# Minimum_MCU_sys.net
KiCad netlist of a schematic drawn in Altium Designer
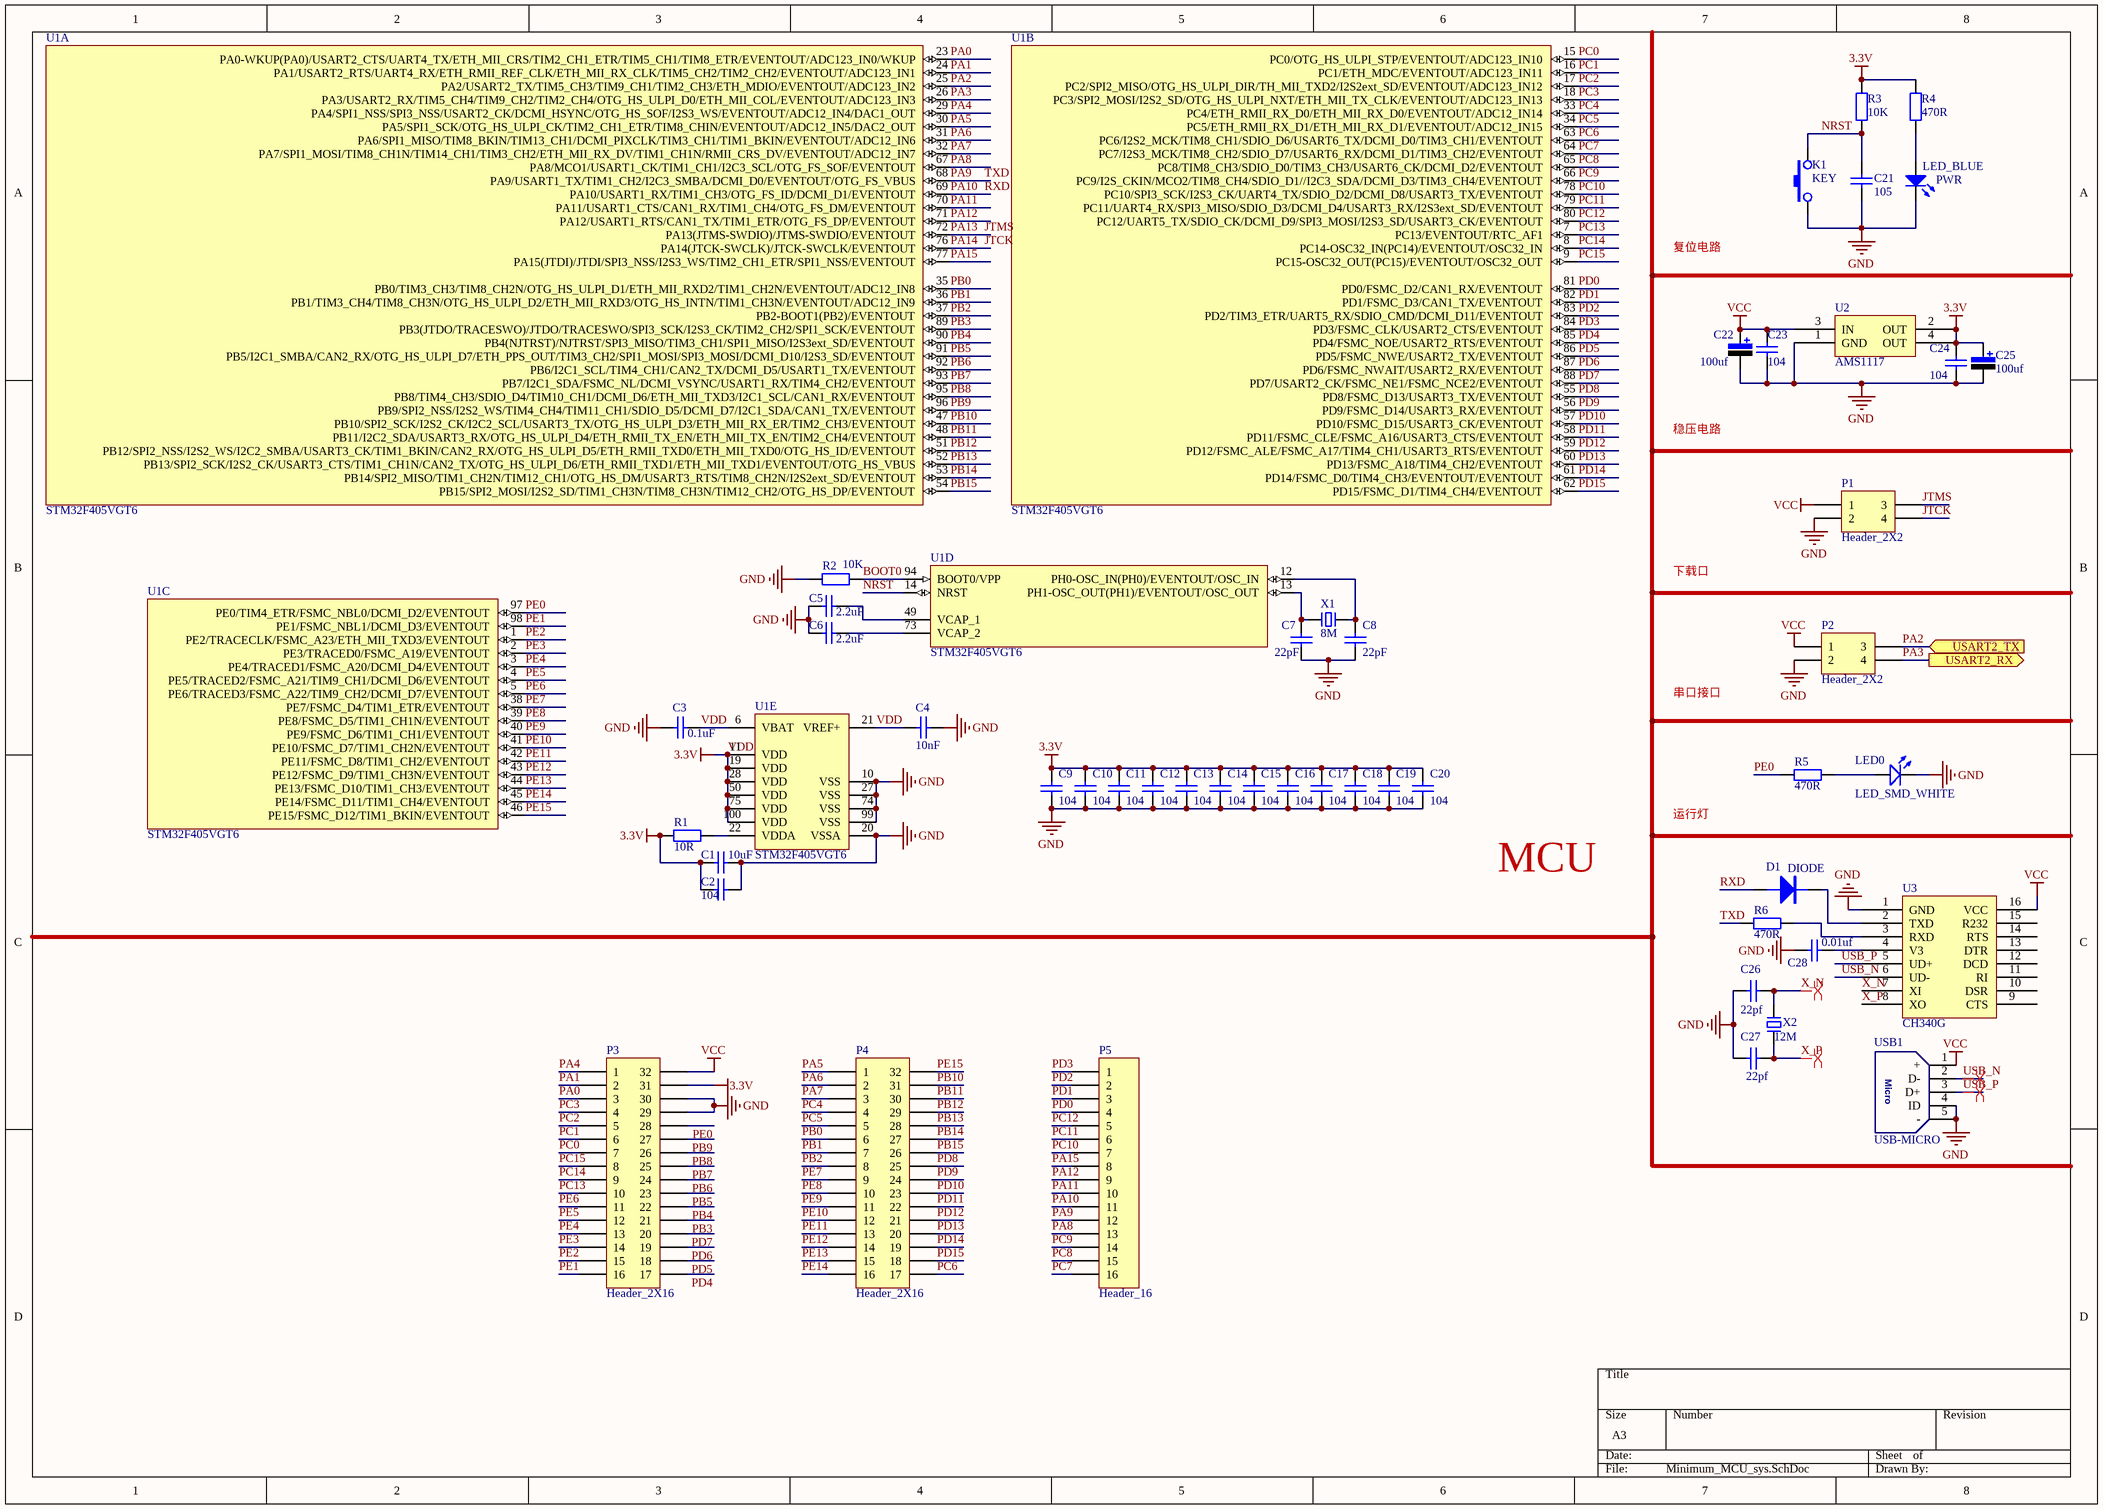
[diagram p0: Minimum_MCU_sys.SchDoc]

(export (version "E")
  (design (tool "Eeschema 10.0.6"))
  (components
    (comp (ref "C1")
      (value "10uF")
      (footprint "Cap-0603")
      (description "贴片陶瓷电容")
      (libsource (lib "Miscellaneous Base") (part "CAP"))
    )
    (comp (ref "C2")
      (value "104")
      (footprint "Cap-0603")
      (description "贴片陶瓷电容")
      (libsource (lib "Miscellaneous Base") (part "CAP"))
    )
    (comp (ref "C3")
      (value "0.1uF")
      (footprint "Cap-0603")
      (description "贴片陶瓷电容")
      (libsource (lib "Miscellaneous Base") (part "CAP"))
    )
    (comp (ref "C4")
      (value "10nF")
      (footprint "Cap-0603")
      (description "贴片陶瓷电容")
      (libsource (lib "Miscellaneous Base") (part "CAP"))
    )
    (comp (ref "C5")
      (value "2.2uF")
      (footprint "Cap-0603")
      (description "贴片陶瓷电容")
      (libsource (lib "Miscellaneous Base") (part "CAP"))
    )
    (comp (ref "C6")
      (value "2.2uF")
      (footprint "Cap-0603")
      (description "贴片陶瓷电容")
      (libsource (lib "Miscellaneous Base") (part "CAP"))
    )
    (comp (ref "C7")
      (value "22pF")
      (footprint "Cap-0603")
      (description "贴片陶瓷电容")
      (libsource (lib "Miscellaneous Base") (part "CAP"))
    )
    (comp (ref "C8")
      (value "22pF")
      (footprint "Cap-0603")
      (description "贴片陶瓷电容")
      (libsource (lib "Miscellaneous Base") (part "CAP"))
    )
    (comp (ref "C9")
      (value "104")
      (footprint "Cap-0603")
      (description "贴片陶瓷电容")
      (libsource (lib "Miscellaneous Base") (part "CAP"))
    )
    (comp (ref "C10")
      (value "104")
      (footprint "Cap-0603")
      (description "贴片陶瓷电容")
      (libsource (lib "Miscellaneous Base") (part "CAP"))
    )
    (comp (ref "C11")
      (value "104")
      (footprint "Cap-0603")
      (description "贴片陶瓷电容")
      (libsource (lib "Miscellaneous Base") (part "CAP"))
    )
    (comp (ref "C12")
      (value "104")
      (footprint "Cap-0603")
      (description "贴片陶瓷电容")
      (libsource (lib "Miscellaneous Base") (part "CAP"))
    )
    (comp (ref "C13")
      (value "104")
      (footprint "Cap-0603")
      (description "贴片陶瓷电容")
      (libsource (lib "Miscellaneous Base") (part "CAP"))
    )
    (comp (ref "C14")
      (value "104")
      (footprint "Cap-0603")
      (description "贴片陶瓷电容")
      (libsource (lib "Miscellaneous Base") (part "CAP"))
    )
    (comp (ref "C15")
      (value "104")
      (footprint "Cap-0603")
      (description "贴片陶瓷电容")
      (libsource (lib "Miscellaneous Base") (part "CAP"))
    )
    (comp (ref "C16")
      (value "104")
      (footprint "Cap-0603")
      (description "贴片陶瓷电容")
      (libsource (lib "Miscellaneous Base") (part "CAP"))
    )
    (comp (ref "C17")
      (value "104")
      (footprint "Cap-0603")
      (description "贴片陶瓷电容")
      (libsource (lib "Miscellaneous Base") (part "CAP"))
    )
    (comp (ref "C18")
      (value "104")
      (footprint "Cap-0603")
      (description "贴片陶瓷电容")
      (libsource (lib "Miscellaneous Base") (part "CAP"))
    )
    (comp (ref "C19")
      (value "104")
      (footprint "Cap-0603")
      (description "贴片陶瓷电容")
      (libsource (lib "Miscellaneous Base") (part "CAP"))
    )
    (comp (ref "C20")
      (value "104")
      (footprint "Cap-0603")
      (description "贴片陶瓷电容")
      (libsource (lib "Miscellaneous Base") (part "CAP"))
    )
    (comp (ref "C21") (value "105") (footprint "Cap-0603") (libsource (lib "最小系统元件库") (part "CAP")))
    (comp (ref "C22") (value "100uf") (footprint "tan_cap_C") (libsource (lib "最小系统元件库") (part "tan_cap")))
    (comp (ref "C23") (value "104") (footprint "Cap-0603-M") (libsource (lib "最小系统元件库") (part "CAP")))
    (comp (ref "C24") (value "104") (footprint "Cap-0603-M") (libsource (lib "最小系统元件库") (part "CAP")))
    (comp (ref "C25") (value "100uf") (footprint "tan_cap_C") (libsource (lib "最小系统元件库") (part "tan_cap")))
    (comp (ref "C26") (value "22pf") (footprint "Cap-0603") (libsource (lib "最小系统元件库") (part "CAP")))
    (comp (ref "C27") (value "22pf") (footprint "Cap-0603") (libsource (lib "最小系统元件库") (part "CAP")))
    (comp (ref "C28") (value "0.01uf") (footprint "Cap-0603") (libsource (lib "base") (part "Cap")))
    (comp (ref "D1")
      (value "DIODE")
      (footprint "SOD-523")
      (description "普通二极管")
      (libsource (lib "Miscellaneous Transistor") (part "DIODE"))
    )
    (comp (ref "K1")
      (value "KEY")
      (footprint "SW-SMD-2X4")
      (libsource (lib "Miscellaneous Switch") (part "KEY"))
    )
    (comp (ref "LED0")
      (value "LED_SMD_WHITE")
      (footprint "LED_0603_W")
      (description "发光二极管")
      (libsource (lib "Miscellaneous Transistor") (part "LED_SMD_WHITE"))
    )
    (comp (ref "P1")
      (value "Header_2X2")
      (footprint "Header_SMD_2.54X2")
      (libsource (lib "Miscellaneous Header") (part "Header_2X2"))
    )
    (comp (ref "P2")
      (value "Header_2X2")
      (footprint "Header_SMD_2.54X2")
      (libsource (lib "Miscellaneous Header") (part "Header_2X2"))
    )
    (comp (ref "P3")
      (value "Header_2X16")
      (footprint "Header 2.54_2X16")
      (libsource (lib "Miscellaneous Header") (part "Header_2X16"))
    )
    (comp (ref "P4")
      (value "Header_2X16")
      (footprint "Header 2.54_2X16")
      (libsource (lib "Miscellaneous Header") (part "Header_2X16"))
    )
    (comp (ref "P5")
      (value "Header_16")
      (footprint "Header 2.54X16")
      (libsource (lib "Miscellaneous Header") (part "Header_16"))
    )
    (comp (ref "PWR")
      (value "LED_BLUE")
      (footprint "LED_0603_B")
      (description "发光二极管")
      (libsource (lib "Miscellaneous Transistor") (part "LED_SMD_BLUE"))
    )
    (comp (ref "R1")
      (value "10R")
      (footprint "Res-0603")
      (description "贴片电阻")
      (libsource (lib "Miscellaneous Base") (part "RES"))
    )
    (comp (ref "R2")
      (value "10K")
      (footprint "Res-0603")
      (description "贴片电阻")
      (libsource (lib "Miscellaneous Base") (part "RES"))
    )
    (comp (ref "R3")
      (value "10K")
      (footprint "Res-0603")
      (description "贴片电阻")
      (libsource (lib "") (part "RES_1"))
    )
    (comp (ref "R4")
      (value "470R")
      (footprint "Res-0603")
      (description "贴片电阻")
      (libsource (lib "") (part "RES_1"))
    )
    (comp (ref "R5")
      (value "470R")
      (footprint "Res-0603")
      (description "贴片电阻")
      (libsource (lib "Miscellaneous Base") (part "RES"))
    )
    (comp (ref "R6")
      (value "470R")
      (footprint "Res-0603")
      (description "贴片电阻")
      (libsource (lib "Miscellaneous Base") (part "RES"))
    )
    (comp (ref "U1")
      (value "STM32F405VGT6")
      (footprint "LQFP100_V")
      (libsource (lib "STMicroelectronics STM32 F4") (part "STM32F405VGT6"))
    )
    (comp (ref "U2") (value "AMS1117") (footprint "AMS1117") (libsource (lib "最小系统元件库") (part "AMS1117")))
    (comp (ref "U3")
      (value "CH340G")
      (footprint "SOP127P590X265-16N")
      (libsource (lib "UperMachineLib") (part "CH340G"))
    )
    (comp (ref "USB1")
      (value "USB-MICRO")
      (footprint "USB-MICRO-SMD_C")
      (libsource (lib "Miscellaneous Socket") (part "USB-MICRO"))
    )
    (comp (ref "X1")
      (value "8M")
      (footprint "OSC 5032-2P")
      (description "2脚无源脚晶振")
      (libsource (lib "Miscellaneous XTAL") (part "XTAL-2P"))
    )
    (comp (ref "X2")
      (value "12M")
      (footprint "OSC 5032-2P")
      (description "2脚无源脚晶振")
      (libsource (lib "Miscellaneous XTAL") (part "XTAL-2P"))
    )
  )
  (nets
    (net (code "1") (name "/BOOT0") (class "Default")
      (node (ref "R2") (pin "2") (pinfunction "2_2") (pintype "passive"))
      (node (ref "U1") (pin "94") (pinfunction "BOOT0/VPP_94") (pintype "input"))
    )
    (net (code "2") (name "/JTCK") (class "Default")
      (node (ref "P1") (pin "4") (pinfunction "4_4") (pintype "passive"))
      (node (ref "U1") (pin "76") (pinfunction "PA14(JTCK-SWCLK)/JTCK-SWCLK/EVENTOUT_76") (pintype "bidirectional"))
    )
    (net (code "3") (name "/JTMS") (class "Default")
      (node (ref "P1") (pin "3") (pinfunction "3_3") (pintype "passive"))
      (node (ref "U1") (pin "72") (pinfunction "PA13(JTMS-SWDIO)/JTMS-SWDIO/EVENTOUT_72") (pintype "bidirectional"))
    )
    (net (code "4") (name "/NRST") (class "Default")
      (node (ref "C21") (pin "2") (pinfunction "2_2") (pintype "passive"))
      (node (ref "K1") (pin "3") (pinfunction "3_3") (pintype "passive"))
      (node (ref "R3") (pin "2") (pinfunction "2_2") (pintype "passive"))
      (node (ref "U1") (pin "14") (pinfunction "NRST_14") (pintype "bidirectional"))
    )
    (net (code "5") (name "/PA0") (class "Default")
      (node (ref "P3") (pin "3") (pinfunction "3_3") (pintype "power_in"))
      (node (ref "U1") (pin "23") (pinfunction "PA0-WKUP(PA0)/USART2_CTS/UART4_TX/ETH_MII_CRS/TIM2_CH1_ETR/TIM5_CH1/TIM8_ETR/EVENTOUT/ADC123_IN0/WKUP_23") (pintype "bidirectional"))
    )
    (net (code "6") (name "/PA1") (class "Default")
      (node (ref "P3") (pin "2") (pinfunction "2_2") (pintype "power_in"))
      (node (ref "U1") (pin "24") (pinfunction "PA1/USART2_RTS/UART4_RX/ETH_RMII_REF_CLK/ETH_MII_RX_CLK/TIM5_CH2/TIM2_CH2/EVENTOUT/ADC123_IN1_24") (pintype "bidirectional"))
    )
    (net (code "7") (name "/PA2") (class "Default")
      (node (ref "P2") (pin "3") (pinfunction "3_3") (pintype "passive"))
      (node (ref "U1") (pin "25") (pinfunction "PA2/USART2_TX/TIM5_CH3/TIM9_CH1/TIM2_CH3/ETH_MDIO/EVENTOUT/ADC123_IN2_25") (pintype "bidirectional"))
    )
    (net (code "8") (name "/PA3") (class "Default")
      (node (ref "P2") (pin "4") (pinfunction "4_4") (pintype "passive"))
      (node (ref "U1") (pin "26") (pinfunction "PA3/USART2_RX/TIM5_CH4/TIM9_CH2/TIM2_CH4/OTG_HS_ULPI_D0/ETH_MII_COL/EVENTOUT/ADC123_IN3_26") (pintype "bidirectional"))
    )
    (net (code "9") (name "/PA4") (class "Default")
      (node (ref "P3") (pin "1") (pinfunction "1_1") (pintype "power_in"))
      (node (ref "U1") (pin "29") (pinfunction "PA4/SPI1_NSS/SPI3_NSS/USART2_CK/DCMI_HSYNC/OTG_HS_SOF/I2S3_WS/EVENTOUT/ADC12_IN4/DAC1_OUT_29") (pintype "bidirectional"))
    )
    (net (code "10") (name "/PA5") (class "Default")
      (node (ref "P4") (pin "1") (pinfunction "1_1") (pintype "power_in"))
      (node (ref "U1") (pin "30") (pinfunction "PA5/SPI1_SCK/OTG_HS_ULPI_CK/TIM2_CH1_ETR/TIM8_CHIN/EVENTOUT/ADC12_IN5/DAC2_OUT_30") (pintype "bidirectional"))
    )
    (net (code "11") (name "/PA6") (class "Default")
      (node (ref "P4") (pin "2") (pinfunction "2_2") (pintype "power_in"))
      (node (ref "U1") (pin "31") (pinfunction "PA6/SPI1_MISO/TIM8_BKIN/TIM13_CH1/DCMI_PIXCLK/TIM3_CH1/TIM1_BKIN/EVENTOUT/ADC12_IN6_31") (pintype "bidirectional"))
    )
    (net (code "12") (name "/PA7") (class "Default")
      (node (ref "P4") (pin "3") (pinfunction "3_3") (pintype "power_in"))
      (node (ref "U1") (pin "32") (pinfunction "PA7/SPI1_MOSI/TIM8_CH1N/TIM14_CH1/TIM3_CH2/ETH_MII_RX_DV/TIM1_CH1N/RMII_CRS_DV/EVENTOUT/ADC12_IN7_32") (pintype "bidirectional"))
    )
    (net (code "13") (name "/PA8") (class "Default")
      (node (ref "P5") (pin "13") (pinfunction "13_13") (pintype "passive"))
      (node (ref "U1") (pin "67") (pinfunction "PA8/MCO1/USART1_CK/TIM1_CH1/I2C3_SCL/OTG_FS_SOF/EVENTOUT_67") (pintype "bidirectional"))
    )
    (net (code "14") (name "/PA9") (class "Default")
      (node (ref "P5") (pin "12") (pinfunction "12_12") (pintype "passive"))
      (node (ref "R6") (pin "1") (pinfunction "1_1") (pintype "passive"))
      (node (ref "U1") (pin "68") (pinfunction "PA9/USART1_TX/TIM1_CH2/I2C3_SMBA/DCMI_D0/EVENTOUT/OTG_FS_VBUS_68") (pintype "bidirectional"))
    )
    (net (code "15") (name "/PA10") (class "Default")
      (node (ref "D1") (pin "A") (pinfunction "A_A") (pintype "passive"))
      (node (ref "P5") (pin "11") (pinfunction "11_11") (pintype "passive"))
      (node (ref "U1") (pin "69") (pinfunction "PA10/USART1_RX/TIM1_CH3/OTG_FS_ID/DCMI_D1/EVENTOUT_69") (pintype "bidirectional"))
    )
    (net (code "16") (name "/PA11") (class "Default")
      (node (ref "P5") (pin "10") (pinfunction "10_10") (pintype "passive"))
      (node (ref "U1") (pin "70") (pinfunction "PA11/USART1_CTS/CAN1_RX/TIM1_CH4/OTG_FS_DM/EVENTOUT_70") (pintype "bidirectional"))
    )
    (net (code "17") (name "/PA12") (class "Default")
      (node (ref "P5") (pin "9") (pinfunction "9_9") (pintype "passive"))
      (node (ref "U1") (pin "71") (pinfunction "PA12/USART1_RTS/CAN1_TX/TIM1_ETR/OTG_FS_DP/EVENTOUT_71") (pintype "bidirectional"))
    )
    (net (code "18") (name "/PA15") (class "Default")
      (node (ref "P5") (pin "8") (pinfunction "8_8") (pintype "passive"))
      (node (ref "U1") (pin "77") (pinfunction "PA15(JTDI)/JTDI/SPI3_NSS/I2S3_WS/TIM2_CH1_ETR/SPI1_NSS/EVENTOUT_77") (pintype "bidirectional"))
    )
    (net (code "19") (name "/PB0") (class "Default")
      (node (ref "P4") (pin "6") (pinfunction "6_6") (pintype "power_in"))
      (node (ref "U1") (pin "35") (pinfunction "PB0/TIM3_CH3/TIM8_CH2N/OTG_HS_ULPI_D1/ETH_MII_RXD2/TIM1_CH2N/EVENTOUT/ADC12_IN8_35") (pintype "bidirectional"))
    )
    (net (code "20") (name "/PB1") (class "Default")
      (node (ref "P4") (pin "7") (pinfunction "7_7") (pintype "power_in"))
      (node (ref "U1") (pin "36") (pinfunction "PB1/TIM3_CH4/TIM8_CH3N/OTG_HS_ULPI_D2/ETH_MII_RXD3/OTG_HS_INTN/TIM1_CH3N/EVENTOUT/ADC12_IN9_36") (pintype "bidirectional"))
    )
    (net (code "21") (name "/PB2") (class "Default")
      (node (ref "P4") (pin "8") (pinfunction "8_8") (pintype "power_in"))
      (node (ref "U1") (pin "37") (pinfunction "PB2-BOOT1(PB2)/EVENTOUT_37") (pintype "bidirectional"))
    )
    (net (code "22") (name "/PB3") (class "Default")
      (node (ref "P3") (pin "21") (pinfunction "21_21") (pintype "power_in"))
      (node (ref "U1") (pin "89") (pinfunction "PB3(JTDO/TRACESWO)/JTDO/TRACESWO/SPI3_SCK/I2S3_CK/TIM2_CH2/SPI1_SCK/EVENTOUT_89") (pintype "bidirectional"))
    )
    (net (code "23") (name "/PB4") (class "Default")
      (node (ref "P3") (pin "22") (pinfunction "22_22") (pintype "power_in"))
      (node (ref "U1") (pin "90") (pinfunction "PB4(NJTRST)/NJTRST/SPI3_MISO/TIM3_CH1/SPI1_MISO/I2S3ext_SD/EVENTOUT_90") (pintype "bidirectional"))
    )
    (net (code "24") (name "/PB5") (class "Default")
      (node (ref "P3") (pin "23") (pinfunction "23_23") (pintype "power_in"))
      (node (ref "U1") (pin "91") (pinfunction "PB5/I2C1_SMBA/CAN2_RX/OTG_HS_ULPI_D7/ETH_PPS_OUT/TIM3_CH2/SPI1_MOSI/SPI3_MOSI/DCMI_D10/I2S3_SD/EVENTOUT_91") (pintype "bidirectional"))
    )
    (net (code "25") (name "/PB6") (class "Default")
      (node (ref "P3") (pin "24") (pinfunction "24_24") (pintype "power_in"))
      (node (ref "U1") (pin "92") (pinfunction "PB6/I2C1_SCL/TIM4_CH1/CAN2_TX/DCMI_D5/USART1_TX/EVENTOUT_92") (pintype "bidirectional"))
    )
    (net (code "26") (name "/PB7") (class "Default")
      (node (ref "P3") (pin "25") (pinfunction "25_25") (pintype "power_in"))
      (node (ref "U1") (pin "93") (pinfunction "PB7/I2C1_SDA/FSMC_NL/DCMI_VSYNC/USART1_RX/TIM4_CH2/EVENTOUT_93") (pintype "bidirectional"))
    )
    (net (code "27") (name "/PB8") (class "Default")
      (node (ref "P3") (pin "26") (pinfunction "26_26") (pintype "power_in"))
      (node (ref "U1") (pin "95") (pinfunction "PB8/TIM4_CH3/SDIO_D4/TIM10_CH1/DCMI_D6/ETH_MII_TXD3/I2C1_SCL/CAN1_RX/EVENTOUT_95") (pintype "bidirectional"))
    )
    (net (code "28") (name "/PB9") (class "Default")
      (node (ref "P3") (pin "27") (pinfunction "27_27") (pintype "power_in"))
      (node (ref "U1") (pin "96") (pinfunction "PB9/SPI2_NSS/I2S2_WS/TIM4_CH4/TIM11_CH1/SDIO_D5/DCMI_D7/I2C1_SDA/CAN1_TX/EVENTOUT_96") (pintype "bidirectional"))
    )
    (net (code "29") (name "/PB10") (class "Default")
      (node (ref "P4") (pin "31") (pinfunction "31_31") (pintype "power_in"))
      (node (ref "U1") (pin "47") (pinfunction "PB10/SPI2_SCK/I2S2_CK/I2C2_SCL/USART3_TX/OTG_HS_ULPI_D3/ETH_MII_RX_ER/TIM2_CH3/EVENTOUT_47") (pintype "bidirectional"))
    )
    (net (code "30") (name "/PB11") (class "Default")
      (node (ref "P4") (pin "30") (pinfunction "30_30") (pintype "power_in"))
      (node (ref "U1") (pin "48") (pinfunction "PB11/I2C2_SDA/USART3_RX/OTG_HS_ULPI_D4/ETH_RMII_TX_EN/ETH_MII_TX_EN/TIM2_CH4/EVENTOUT_48") (pintype "bidirectional"))
    )
    (net (code "31") (name "/PB12") (class "Default")
      (node (ref "P4") (pin "29") (pinfunction "29_29") (pintype "power_in"))
      (node (ref "U1") (pin "51") (pinfunction "PB12/SPI2_NSS/I2S2_WS/I2C2_SMBA/USART3_CK/TIM1_BKIN/CAN2_RX/OTG_HS_ULPI_D5/ETH_RMII_TXD0/ETH_MII_TXD0/OTG_HS_ID/EVENTOUT_51") (pintype "bidirectional"))
    )
    (net (code "32") (name "/PB13") (class "Default")
      (node (ref "P4") (pin "28") (pinfunction "28_28") (pintype "power_in"))
      (node (ref "U1") (pin "52") (pinfunction "PB13/SPI2_SCK/I2S2_CK/USART3_CTS/TIM1_CH1N/CAN2_TX/OTG_HS_ULPI_D6/ETH_RMII_TXD1/ETH_MII_TXD1/EVENTOUT/OTG_HS_VBUS_52") (pintype "bidirectional"))
    )
    (net (code "33") (name "/PB14") (class "Default")
      (node (ref "P4") (pin "27") (pinfunction "27_27") (pintype "power_in"))
      (node (ref "U1") (pin "53") (pinfunction "PB14/SPI2_MISO/TIM1_CH2N/TIM12_CH1/OTG_HS_DM/USART3_RTS/TIM8_CH2N/I2S2ext_SD/EVENTOUT_53") (pintype "bidirectional"))
    )
    (net (code "34") (name "/PB15") (class "Default")
      (node (ref "P4") (pin "26") (pinfunction "26_26") (pintype "power_in"))
      (node (ref "U1") (pin "54") (pinfunction "PB15/SPI2_MOSI/I2S2_SD/TIM1_CH3N/TIM8_CH3N/TIM12_CH2/OTG_HS_DP/EVENTOUT_54") (pintype "bidirectional"))
    )
    (net (code "35") (name "/PC0") (class "Default")
      (node (ref "P3") (pin "7") (pinfunction "7_7") (pintype "power_in"))
      (node (ref "U1") (pin "15") (pinfunction "PC0/OTG_HS_ULPI_STP/EVENTOUT/ADC123_IN10_15") (pintype "bidirectional"))
    )
    (net (code "36") (name "/PC1") (class "Default")
      (node (ref "P3") (pin "6") (pinfunction "6_6") (pintype "power_in"))
      (node (ref "U1") (pin "16") (pinfunction "PC1/ETH_MDC/EVENTOUT/ADC123_IN11_16") (pintype "bidirectional"))
    )
    (net (code "37") (name "/PC2") (class "Default")
      (node (ref "P3") (pin "5") (pinfunction "5_5") (pintype "power_in"))
      (node (ref "U1") (pin "17") (pinfunction "PC2/SPI2_MISO/OTG_HS_ULPI_DIR/TH_MII_TXD2/I2S2ext_SD/EVENTOUT/ADC123_IN12_17") (pintype "bidirectional"))
    )
    (net (code "38") (name "/PC3") (class "Default")
      (node (ref "P3") (pin "4") (pinfunction "4_4") (pintype "power_in"))
      (node (ref "U1") (pin "18") (pinfunction "PC3/SPI2_MOSI/I2S2_SD/OTG_HS_ULPI_NXT/ETH_MII_TX_CLK/EVENTOUT/ADC123_IN13_18") (pintype "bidirectional"))
    )
    (net (code "39") (name "/PC4") (class "Default")
      (node (ref "P4") (pin "4") (pinfunction "4_4") (pintype "power_in"))
      (node (ref "U1") (pin "33") (pinfunction "PC4/ETH_RMII_RX_D0/ETH_MII_RX_D0/EVENTOUT/ADC12_IN14_33") (pintype "bidirectional"))
    )
    (net (code "40") (name "/PC5") (class "Default")
      (node (ref "P4") (pin "5") (pinfunction "5_5") (pintype "power_in"))
      (node (ref "U1") (pin "34") (pinfunction "PC5/ETH_RMII_RX_D1/ETH_MII_RX_D1/EVENTOUT/ADC12_IN15_34") (pintype "bidirectional"))
    )
    (net (code "41") (name "/PC6") (class "Default")
      (node (ref "P4") (pin "17") (pinfunction "17_17") (pintype "power_in"))
      (node (ref "U1") (pin "63") (pinfunction "PC6/I2S2_MCK/TIM8_CH1/SDIO_D6/USART6_TX/DCMI_D0/TIM3_CH1/EVENTOUT_63") (pintype "bidirectional"))
    )
    (net (code "42") (name "/PC7") (class "Default")
      (node (ref "P5") (pin "16") (pinfunction "16_16") (pintype "passive"))
      (node (ref "U1") (pin "64") (pinfunction "PC7/I2S3_MCK/TIM8_CH2/SDIO_D7/USART6_RX/DCMI_D1/TIM3_CH2/EVENTOUT_64") (pintype "bidirectional"))
    )
    (net (code "43") (name "/PC8") (class "Default")
      (node (ref "P5") (pin "15") (pinfunction "15_15") (pintype "passive"))
      (node (ref "U1") (pin "65") (pinfunction "PC8/TIM8_CH3/SDIO_D0/TIM3_CH3/USART6_CK/DCMI_D2/EVENTOUT_65") (pintype "bidirectional"))
    )
    (net (code "44") (name "/PC9") (class "Default")
      (node (ref "P5") (pin "14") (pinfunction "14_14") (pintype "passive"))
      (node (ref "U1") (pin "66") (pinfunction "PC9/I2S_CKIN/MCO2/TIM8_CH4/SDIO_D1//I2C3_SDA/DCMI_D3/TIM3_CH4/EVENTOUT_66") (pintype "bidirectional"))
    )
    (net (code "45") (name "/PC10") (class "Default")
      (node (ref "P5") (pin "7") (pinfunction "7_7") (pintype "passive"))
      (node (ref "U1") (pin "78") (pinfunction "PC10/SPI3_SCK/I2S3_CK/UART4_TX/SDIO_D2/DCMI_D8/USART3_TX/EVENTOUT_78") (pintype "bidirectional"))
    )
    (net (code "46") (name "/PC11") (class "Default")
      (node (ref "P5") (pin "6") (pinfunction "6_6") (pintype "passive"))
      (node (ref "U1") (pin "79") (pinfunction "PC11/UART4_RX/SPI3_MISO/SDIO_D3/DCMI_D4/USART3_RX/I2S3ext_SD/EVENTOUT_79") (pintype "bidirectional"))
    )
    (net (code "47") (name "/PC12") (class "Default")
      (node (ref "P5") (pin "5") (pinfunction "5_5") (pintype "passive"))
      (node (ref "U1") (pin "80") (pinfunction "PC12/UART5_TX/SDIO_CK/DCMI_D9/SPI3_MOSI/I2S3_SD/USART3_CK/EVENTOUT_80") (pintype "bidirectional"))
    )
    (net (code "48") (name "/PC13") (class "Default")
      (node (ref "P3") (pin "10") (pinfunction "10_10") (pintype "power_in"))
      (node (ref "U1") (pin "7") (pinfunction "PC13/EVENTOUT/RTC_AF1_7") (pintype "bidirectional"))
    )
    (net (code "49") (name "/PC14") (class "Default")
      (node (ref "P3") (pin "9") (pinfunction "9_9") (pintype "power_in"))
      (node (ref "U1") (pin "8") (pinfunction "PC14-OSC32_IN(PC14)/EVENTOUT/OSC32_IN_8") (pintype "bidirectional"))
    )
    (net (code "50") (name "/PC15") (class "Default")
      (node (ref "P3") (pin "8") (pinfunction "8_8") (pintype "power_in"))
      (node (ref "U1") (pin "9") (pinfunction "PC15-OSC32_OUT(PC15)/EVENTOUT/OSC32_OUT_9") (pintype "bidirectional"))
    )
    (net (code "51") (name "/PD0") (class "Default")
      (node (ref "P5") (pin "4") (pinfunction "4_4") (pintype "passive"))
      (node (ref "U1") (pin "81") (pinfunction "PD0/FSMC_D2/CAN1_RX/EVENTOUT_81") (pintype "bidirectional"))
    )
    (net (code "52") (name "/PD1") (class "Default")
      (node (ref "P5") (pin "3") (pinfunction "3_3") (pintype "passive"))
      (node (ref "U1") (pin "82") (pinfunction "PD1/FSMC_D3/CAN1_TX/EVENTOUT_82") (pintype "bidirectional"))
    )
    (net (code "53") (name "/PD2") (class "Default")
      (node (ref "P5") (pin "2") (pinfunction "2_2") (pintype "passive"))
      (node (ref "U1") (pin "83") (pinfunction "PD2/TIM3_ETR/UART5_RX/SDIO_CMD/DCMI_D11/EVENTOUT_83") (pintype "bidirectional"))
    )
    (net (code "54") (name "/PD3") (class "Default")
      (node (ref "P5") (pin "1") (pinfunction "1_1") (pintype "passive"))
      (node (ref "U1") (pin "84") (pinfunction "PD3/FSMC_CLK/USART2_CTS/EVENTOUT_84") (pintype "bidirectional"))
    )
    (net (code "55") (name "/PD4") (class "Default")
      (node (ref "P3") (pin "17") (pinfunction "17_17") (pintype "power_in"))
      (node (ref "U1") (pin "85") (pinfunction "PD4/FSMC_NOE/USART2_RTS/EVENTOUT_85") (pintype "bidirectional"))
    )
    (net (code "56") (name "/PD5") (class "Default")
      (node (ref "P3") (pin "18") (pinfunction "18_18") (pintype "power_in"))
      (node (ref "U1") (pin "86") (pinfunction "PD5/FSMC_NWE/USART2_TX/EVENTOUT_86") (pintype "bidirectional"))
    )
    (net (code "57") (name "/PD6") (class "Default")
      (node (ref "P3") (pin "19") (pinfunction "19_19") (pintype "power_in"))
      (node (ref "U1") (pin "87") (pinfunction "PD6/FSMC_NWAIT/USART2_RX/EVENTOUT_87") (pintype "bidirectional"))
    )
    (net (code "58") (name "/PD7") (class "Default")
      (node (ref "P3") (pin "20") (pinfunction "20_20") (pintype "power_in"))
      (node (ref "U1") (pin "88") (pinfunction "PD7/USART2_CK/FSMC_NE1/FSMC_NCE2/EVENTOUT_88") (pintype "bidirectional"))
    )
    (net (code "59") (name "/PD8") (class "Default")
      (node (ref "P4") (pin "25") (pinfunction "25_25") (pintype "power_in"))
      (node (ref "U1") (pin "55") (pinfunction "PD8/FSMC_D13/USART3_TX/EVENTOUT_55") (pintype "bidirectional"))
    )
    (net (code "60") (name "/PD9") (class "Default")
      (node (ref "P4") (pin "24") (pinfunction "24_24") (pintype "power_in"))
      (node (ref "U1") (pin "56") (pinfunction "PD9/FSMC_D14/USART3_RX/EVENTOUT_56") (pintype "bidirectional"))
    )
    (net (code "61") (name "/PD10") (class "Default")
      (node (ref "P4") (pin "23") (pinfunction "23_23") (pintype "power_in"))
      (node (ref "U1") (pin "57") (pinfunction "PD10/FSMC_D15/USART3_CK/EVENTOUT_57") (pintype "bidirectional"))
    )
    (net (code "62") (name "/PD11") (class "Default")
      (node (ref "P4") (pin "22") (pinfunction "22_22") (pintype "power_in"))
      (node (ref "U1") (pin "58") (pinfunction "PD11/FSMC_CLE/FSMC_A16/USART3_CTS/EVENTOUT_58") (pintype "bidirectional"))
    )
    (net (code "63") (name "/PD12") (class "Default")
      (node (ref "P4") (pin "21") (pinfunction "21_21") (pintype "power_in"))
      (node (ref "U1") (pin "59") (pinfunction "PD12/FSMC_ALE/FSMC_A17/TIM4_CH1/USART3_RTS/EVENTOUT_59") (pintype "bidirectional"))
    )
    (net (code "64") (name "/PD13") (class "Default")
      (node (ref "P4") (pin "20") (pinfunction "20_20") (pintype "power_in"))
      (node (ref "U1") (pin "60") (pinfunction "PD13/FSMC_A18/TIM4_CH2/EVENTOUT_60") (pintype "bidirectional"))
    )
    (net (code "65") (name "/PD14") (class "Default")
      (node (ref "P4") (pin "19") (pinfunction "19_19") (pintype "power_in"))
      (node (ref "U1") (pin "61") (pinfunction "PD14/FSMC_D0/TIM4_CH3/EVENTOUT/EVENTOUT_61") (pintype "bidirectional"))
    )
    (net (code "66") (name "/PD15") (class "Default")
      (node (ref "P4") (pin "18") (pinfunction "18_18") (pintype "power_in"))
      (node (ref "U1") (pin "62") (pinfunction "PD15/FSMC_D1/TIM4_CH4/EVENTOUT_62") (pintype "bidirectional"))
    )
    (net (code "67") (name "/PE0") (class "Default")
      (node (ref "P3") (pin "28") (pinfunction "28_28") (pintype "power_in"))
      (node (ref "R5") (pin "1") (pinfunction "1_1") (pintype "passive"))
      (node (ref "U1") (pin "97") (pinfunction "PE0/TIM4_ETR/FSMC_NBL0/DCMI_D2/EVENTOUT_97") (pintype "bidirectional"))
    )
    (net (code "68") (name "/PE1") (class "Default")
      (node (ref "P3") (pin "16") (pinfunction "16_16") (pintype "power_in"))
      (node (ref "U1") (pin "98") (pinfunction "PE1/FSMC_NBL1/DCMI_D3/EVENTOUT_98") (pintype "bidirectional"))
    )
    (net (code "69") (name "/PE2") (class "Default")
      (node (ref "P3") (pin "15") (pinfunction "15_15") (pintype "power_in"))
      (node (ref "U1") (pin "1") (pinfunction "PE2/TRACECLK/FSMC_A23/ETH_MII_TXD3/EVENTOUT_1") (pintype "bidirectional"))
    )
    (net (code "70") (name "/PE3") (class "Default")
      (node (ref "P3") (pin "14") (pinfunction "14_14") (pintype "power_in"))
      (node (ref "U1") (pin "2") (pinfunction "PE3/TRACED0/FSMC_A19/EVENTOUT_2") (pintype "bidirectional"))
    )
    (net (code "71") (name "/PE4") (class "Default")
      (node (ref "P3") (pin "13") (pinfunction "13_13") (pintype "power_in"))
      (node (ref "U1") (pin "3") (pinfunction "PE4/TRACED1/FSMC_A20/DCMI_D4/EVENTOUT_3") (pintype "bidirectional"))
    )
    (net (code "72") (name "/PE5") (class "Default")
      (node (ref "P3") (pin "12") (pinfunction "12_12") (pintype "power_in"))
      (node (ref "U1") (pin "4") (pinfunction "PE5/TRACED2/FSMC_A21/TIM9_CH1/DCMI_D6/EVENTOUT_4") (pintype "bidirectional"))
    )
    (net (code "73") (name "/PE6") (class "Default")
      (node (ref "P3") (pin "11") (pinfunction "11_11") (pintype "power_in"))
      (node (ref "U1") (pin "5") (pinfunction "PE6/TRACED3/FSMC_A22/TIM9_CH2/DCMI_D7/EVENTOUT_5") (pintype "bidirectional"))
    )
    (net (code "74") (name "/PE7") (class "Default")
      (node (ref "P4") (pin "9") (pinfunction "9_9") (pintype "power_in"))
      (node (ref "U1") (pin "38") (pinfunction "PE7/FSMC_D4/TIM1_ETR/EVENTOUT_38") (pintype "bidirectional"))
    )
    (net (code "75") (name "/PE8") (class "Default")
      (node (ref "P4") (pin "10") (pinfunction "10_10") (pintype "power_in"))
      (node (ref "U1") (pin "39") (pinfunction "PE8/FSMC_D5/TIM1_CH1N/EVENTOUT_39") (pintype "bidirectional"))
    )
    (net (code "76") (name "/PE9") (class "Default")
      (node (ref "P4") (pin "11") (pinfunction "11_11") (pintype "power_in"))
      (node (ref "U1") (pin "40") (pinfunction "PE9/FSMC_D6/TIM1_CH1/EVENTOUT_40") (pintype "bidirectional"))
    )
    (net (code "77") (name "/PE10") (class "Default")
      (node (ref "P4") (pin "12") (pinfunction "12_12") (pintype "power_in"))
      (node (ref "U1") (pin "41") (pinfunction "PE10/FSMC_D7/TIM1_CH2N/EVENTOUT_41") (pintype "bidirectional"))
    )
    (net (code "78") (name "/PE11") (class "Default")
      (node (ref "P4") (pin "13") (pinfunction "13_13") (pintype "power_in"))
      (node (ref "U1") (pin "42") (pinfunction "PE11/FSMC_D8/TIM1_CH2/EVENTOUT_42") (pintype "bidirectional"))
    )
    (net (code "79") (name "/PE12") (class "Default")
      (node (ref "P4") (pin "14") (pinfunction "14_14") (pintype "power_in"))
      (node (ref "U1") (pin "43") (pinfunction "PE12/FSMC_D9/TIM1_CH3N/EVENTOUT_43") (pintype "bidirectional"))
    )
    (net (code "80") (name "/PE13") (class "Default")
      (node (ref "P4") (pin "15") (pinfunction "15_15") (pintype "power_in"))
      (node (ref "U1") (pin "44") (pinfunction "PE13/FSMC_D10/TIM1_CH3/EVENTOUT_44") (pintype "bidirectional"))
    )
    (net (code "81") (name "/PE14") (class "Default")
      (node (ref "P4") (pin "16") (pinfunction "16_16") (pintype "power_in"))
      (node (ref "U1") (pin "45") (pinfunction "PE14/FSMC_D11/TIM1_CH4/EVENTOUT_45") (pintype "bidirectional"))
    )
    (net (code "82") (name "/PE15") (class "Default")
      (node (ref "P4") (pin "32") (pinfunction "32_32") (pintype "power_in"))
      (node (ref "U1") (pin "46") (pinfunction "PE15/FSMC_D12/TIM1_BKIN/EVENTOUT_46") (pintype "bidirectional"))
    )
    (net (code "83") (name "/USB_N") (class "Default")
      (node (ref "U3") (pin "6") (pinfunction "UD-_6") (pintype "passive"))
      (node (ref "USB1") (pin "2") (pinfunction "D-_2") (pintype "passive"))
    )
    (net (code "84") (name "/USB_P") (class "Default")
      (node (ref "U3") (pin "5") (pinfunction "UD+_5") (pintype "passive"))
      (node (ref "USB1") (pin "3") (pinfunction "D+_3") (pintype "passive"))
    )
    (net (code "85") (name "/X_N") (class "Default")
      (node (ref "C26") (pin "1") (pinfunction "1_1") (pintype "passive"))
      (node (ref "U3") (pin "7") (pinfunction "XI_7") (pintype "passive"))
      (node (ref "X2") (pin "1") (pinfunction "1_1") (pintype "passive"))
    )
    (net (code "86") (name "/X_P") (class "Default")
      (node (ref "C27") (pin "1") (pinfunction "1_1") (pintype "passive"))
      (node (ref "U3") (pin "8") (pinfunction "XO_8") (pintype "passive"))
      (node (ref "X2") (pin "2") (pinfunction "2_2") (pintype "passive"))
    )
    (net (code "87") (name "3.3V") (class "Default")
      (node (ref "C1") (pin "1") (pinfunction "1_1") (pintype "passive"))
      (node (ref "C10") (pin "2") (pinfunction "2_2") (pintype "passive"))
      (node (ref "C11") (pin "2") (pinfunction "2_2") (pintype "passive"))
      (node (ref "C12") (pin "2") (pinfunction "2_2") (pintype "passive"))
      (node (ref "C13") (pin "2") (pinfunction "2_2") (pintype "passive"))
      (node (ref "C14") (pin "2") (pinfunction "2_2") (pintype "passive"))
      (node (ref "C15") (pin "2") (pinfunction "2_2") (pintype "passive"))
      (node (ref "C16") (pin "2") (pinfunction "2_2") (pintype "passive"))
      (node (ref "C17") (pin "2") (pinfunction "2_2") (pintype "passive"))
      (node (ref "C18") (pin "2") (pinfunction "2_2") (pintype "passive"))
      (node (ref "C19") (pin "2") (pinfunction "2_2") (pintype "passive"))
      (node (ref "C2") (pin "1") (pinfunction "1_1") (pintype "passive"))
      (node (ref "C20") (pin "2") (pinfunction "2_2") (pintype "passive"))
      (node (ref "C24") (pin "2") (pinfunction "2_2") (pintype "passive"))
      (node (ref "C25") (pin "1") (pinfunction "1_1") (pintype "passive"))
      (node (ref "C3") (pin "2") (pinfunction "2_2") (pintype "passive"))
      (node (ref "C4") (pin "2") (pinfunction "2_2") (pintype "passive"))
      (node (ref "C9") (pin "2") (pinfunction "2_2") (pintype "passive"))
      (node (ref "P3") (pin "31") (pinfunction "31_31") (pintype "power_in"))
      (node (ref "R1") (pin "1") (pinfunction "1_1") (pintype "passive"))
      (node (ref "R3") (pin "1") (pinfunction "1_1") (pintype "passive"))
      (node (ref "R4") (pin "1") (pinfunction "1_1") (pintype "passive"))
      (node (ref "U1") (pin "100") (pinfunction "VDD_100") (pintype "power_in"))
      (node (ref "U1") (pin "11") (pinfunction "VDD_11") (pintype "power_in"))
      (node (ref "U1") (pin "19") (pinfunction "VDD_19") (pintype "power_in"))
      (node (ref "U1") (pin "21") (pinfunction "VREF+_21") (pintype "power_in"))
      (node (ref "U1") (pin "28") (pinfunction "VDD_28") (pintype "power_in"))
      (node (ref "U1") (pin "50") (pinfunction "VDD_50") (pintype "power_in"))
      (node (ref "U1") (pin "6") (pinfunction "VBAT_6") (pintype "power_in"))
      (node (ref "U1") (pin "75") (pinfunction "VDD_75") (pintype "power_in"))
      (node (ref "U2") (pin "2") (pinfunction "OUT_2") (pintype "passive"))
      (node (ref "U2") (pin "4") (pinfunction "OUT_4") (pintype "passive"))
    )
    (net (code "88") (name "GND") (class "Default")
      (node (ref "C1") (pin "2") (pinfunction "2_2") (pintype "passive"))
      (node (ref "C10") (pin "1") (pinfunction "1_1") (pintype "passive"))
      (node (ref "C11") (pin "1") (pinfunction "1_1") (pintype "passive"))
      (node (ref "C12") (pin "1") (pinfunction "1_1") (pintype "passive"))
      (node (ref "C13") (pin "1") (pinfunction "1_1") (pintype "passive"))
      (node (ref "C14") (pin "1") (pinfunction "1_1") (pintype "passive"))
      (node (ref "C15") (pin "1") (pinfunction "1_1") (pintype "passive"))
      (node (ref "C16") (pin "1") (pinfunction "1_1") (pintype "passive"))
      (node (ref "C17") (pin "1") (pinfunction "1_1") (pintype "passive"))
      (node (ref "C18") (pin "1") (pinfunction "1_1") (pintype "passive"))
      (node (ref "C19") (pin "1") (pinfunction "1_1") (pintype "passive"))
      (node (ref "C2") (pin "2") (pinfunction "2_2") (pintype "passive"))
      (node (ref "C20") (pin "1") (pinfunction "1_1") (pintype "passive"))
      (node (ref "C21") (pin "1") (pinfunction "1_1") (pintype "passive"))
      (node (ref "C22") (pin "2") (pinfunction "2_2") (pintype "passive"))
      (node (ref "C23") (pin "1") (pinfunction "1_1") (pintype "passive"))
      (node (ref "C24") (pin "1") (pinfunction "1_1") (pintype "passive"))
      (node (ref "C25") (pin "2") (pinfunction "2_2") (pintype "passive"))
      (node (ref "C26") (pin "2") (pinfunction "2_2") (pintype "passive"))
      (node (ref "C27") (pin "2") (pinfunction "2_2") (pintype "passive"))
      (node (ref "C28") (pin "1") (pinfunction "1_1") (pintype "passive"))
      (node (ref "C3") (pin "1") (pinfunction "1_1") (pintype "passive"))
      (node (ref "C4") (pin "1") (pinfunction "1_1") (pintype "passive"))
      (node (ref "C5") (pin "1") (pinfunction "1_1") (pintype "passive"))
      (node (ref "C6") (pin "1") (pinfunction "1_1") (pintype "passive"))
      (node (ref "C7") (pin "2") (pinfunction "2_2") (pintype "passive"))
      (node (ref "C8") (pin "1") (pinfunction "1_1") (pintype "passive"))
      (node (ref "C9") (pin "1") (pinfunction "1_1") (pintype "passive"))
      (node (ref "K1") (pin "1") (pinfunction "1_1") (pintype "passive"))
      (node (ref "LED0") (pin "2") (pinfunction "K_2") (pintype "passive"))
      (node (ref "P1") (pin "2") (pinfunction "2_2") (pintype "passive"))
      (node (ref "P2") (pin "2") (pinfunction "2_2") (pintype "passive"))
      (node (ref "P3") (pin "29") (pinfunction "29_29") (pintype "power_in"))
      (node (ref "P3") (pin "30") (pinfunction "30_30") (pintype "power_in"))
      (node (ref "PWR") (pin "2") (pinfunction "K_2") (pintype "passive"))
      (node (ref "R2") (pin "1") (pinfunction "1_1") (pintype "passive"))
      (node (ref "U1") (pin "10") (pinfunction "VSS_10") (pintype "power_in"))
      (node (ref "U1") (pin "20") (pinfunction "VSSA_20") (pintype "power_in"))
      (node (ref "U1") (pin "27") (pinfunction "VSS_27") (pintype "power_in"))
      (node (ref "U1") (pin "74") (pinfunction "VSS_74") (pintype "power_in"))
      (node (ref "U1") (pin "99") (pinfunction "VSS_99") (pintype "power_in"))
      (node (ref "U2") (pin "1") (pinfunction "GND_1") (pintype "passive"))
      (node (ref "U3") (pin "1") (pinfunction "GND_1") (pintype "passive"))
      (node (ref "USB1") (pin "4") (pinfunction "ID_4") (pintype "passive"))
      (node (ref "USB1") (pin "5") (pinfunction "-_5") (pintype "passive"))
    )
    (net (code "89") (name "Net-(LED0-A)") (class "Default")
      (node (ref "LED0") (pin "1") (pinfunction "A_1") (pintype "passive"))
      (node (ref "R5") (pin "2") (pinfunction "2_2") (pintype "passive"))
    )
    (net (code "90") (name "Net-(PWR-A)") (class "Default")
      (node (ref "PWR") (pin "1") (pinfunction "A_1") (pintype "passive"))
      (node (ref "R4") (pin "2") (pinfunction "2_2") (pintype "passive"))
    )
    (net (code "91") (name "Net-(U1D-PH0-OSC_IN(PH0){slash}EVENTOUT{slash}OSC_IN)") (class "Default")
      (node (ref "C8") (pin "2") (pinfunction "2_2") (pintype "passive"))
      (node (ref "U1") (pin "12") (pinfunction "PH0-OSC_IN(PH0)/EVENTOUT/OSC_IN_12") (pintype "bidirectional"))
      (node (ref "X1") (pin "1") (pinfunction "1_1") (pintype "passive"))
    )
    (net (code "92") (name "Net-(U1D-PH1-OSC_OUT(PH1){slash}EVENTOUT{slash}OSC_OUT)") (class "Default")
      (node (ref "C7") (pin "1") (pinfunction "1_1") (pintype "passive"))
      (node (ref "U1") (pin "13") (pinfunction "PH1-OSC_OUT(PH1)/EVENTOUT/OSC_OUT_13") (pintype "bidirectional"))
      (node (ref "X1") (pin "2") (pinfunction "2_2") (pintype "passive"))
    )
    (net (code "93") (name "Net-(U1D-VCAP_1)") (class "Default")
      (node (ref "C5") (pin "2") (pinfunction "2_2") (pintype "passive"))
      (node (ref "U1") (pin "49") (pinfunction "VCAP_1_49") (pintype "power_in"))
    )
    (net (code "94") (name "Net-(U1D-VCAP_2)") (class "Default")
      (node (ref "C6") (pin "2") (pinfunction "2_2") (pintype "passive"))
      (node (ref "U1") (pin "73") (pinfunction "VCAP_2_73") (pintype "power_in"))
    )
    (net (code "95") (name "Net-(U1E-VDDA)") (class "Default")
      (node (ref "R1") (pin "2") (pinfunction "2_2") (pintype "passive"))
      (node (ref "U1") (pin "22") (pinfunction "VDDA_22") (pintype "power_in"))
    )
    (net (code "96") (name "Net-(U3-RXD)") (class "Default")
      (node (ref "R6") (pin "2") (pinfunction "2_2") (pintype "passive"))
      (node (ref "U3") (pin "3") (pinfunction "RXD_3") (pintype "passive"))
    )
    (net (code "97") (name "Net-(U3-TXD)") (class "Default")
      (node (ref "D1") (pin "K") (pinfunction "K_K") (pintype "passive"))
      (node (ref "U3") (pin "2") (pinfunction "TXD_2") (pintype "passive"))
    )
    (net (code "98") (name "Net-(U3-V3)") (class "Default")
      (node (ref "C28") (pin "2") (pinfunction "2_2") (pintype "passive"))
      (node (ref "U3") (pin "4") (pinfunction "V3_4") (pintype "passive"))
    )
    (net (code "99") (name "VCC") (class "Default")
      (node (ref "C22") (pin "1") (pinfunction "1_1") (pintype "passive"))
      (node (ref "C23") (pin "2") (pinfunction "2_2") (pintype "passive"))
      (node (ref "P1") (pin "1") (pinfunction "1_1") (pintype "passive"))
      (node (ref "P2") (pin "1") (pinfunction "1_1") (pintype "passive"))
      (node (ref "P3") (pin "32") (pinfunction "32_32") (pintype "power_in"))
      (node (ref "U2") (pin "3") (pinfunction "IN_3") (pintype "passive"))
      (node (ref "U3") (pin "16") (pinfunction "VCC_16") (pintype "passive"))
      (node (ref "USB1") (pin "1") (pinfunction "+_1") (pintype "passive"))
    )
    (net (code "100") (name "unconnected-(U3-CTS-Pad9)") (class "Default")
      (node (ref "U3") (pin "9") (pinfunction "CTS_9") (pintype "passive"))
    )
    (net (code "101") (name "unconnected-(U3-DCD-Pad12)") (class "Default")
      (node (ref "U3") (pin "12") (pinfunction "DCD_12") (pintype "passive"))
    )
    (net (code "102") (name "unconnected-(U3-DSR-Pad10)") (class "Default")
      (node (ref "U3") (pin "10") (pinfunction "DSR_10") (pintype "passive"))
    )
    (net (code "103") (name "unconnected-(U3-DTR-Pad13)") (class "Default")
      (node (ref "U3") (pin "13") (pinfunction "DTR_13") (pintype "passive"))
    )
    (net (code "104") (name "unconnected-(U3-R232-Pad15)") (class "Default")
      (node (ref "U3") (pin "15") (pinfunction "R232_15") (pintype "passive"))
    )
    (net (code "105") (name "unconnected-(U3-RI-Pad11)") (class "Default")
      (node (ref "U3") (pin "11") (pinfunction "RI_11") (pintype "passive"))
    )
    (net (code "106") (name "unconnected-(U3-RTS-Pad14)") (class "Default")
      (node (ref "U3") (pin "14") (pinfunction "RTS_14") (pintype "passive"))
    )
  )
)
